# mbgw_teensy.net
KiCad netlist of a schematic drawn in EAGLE
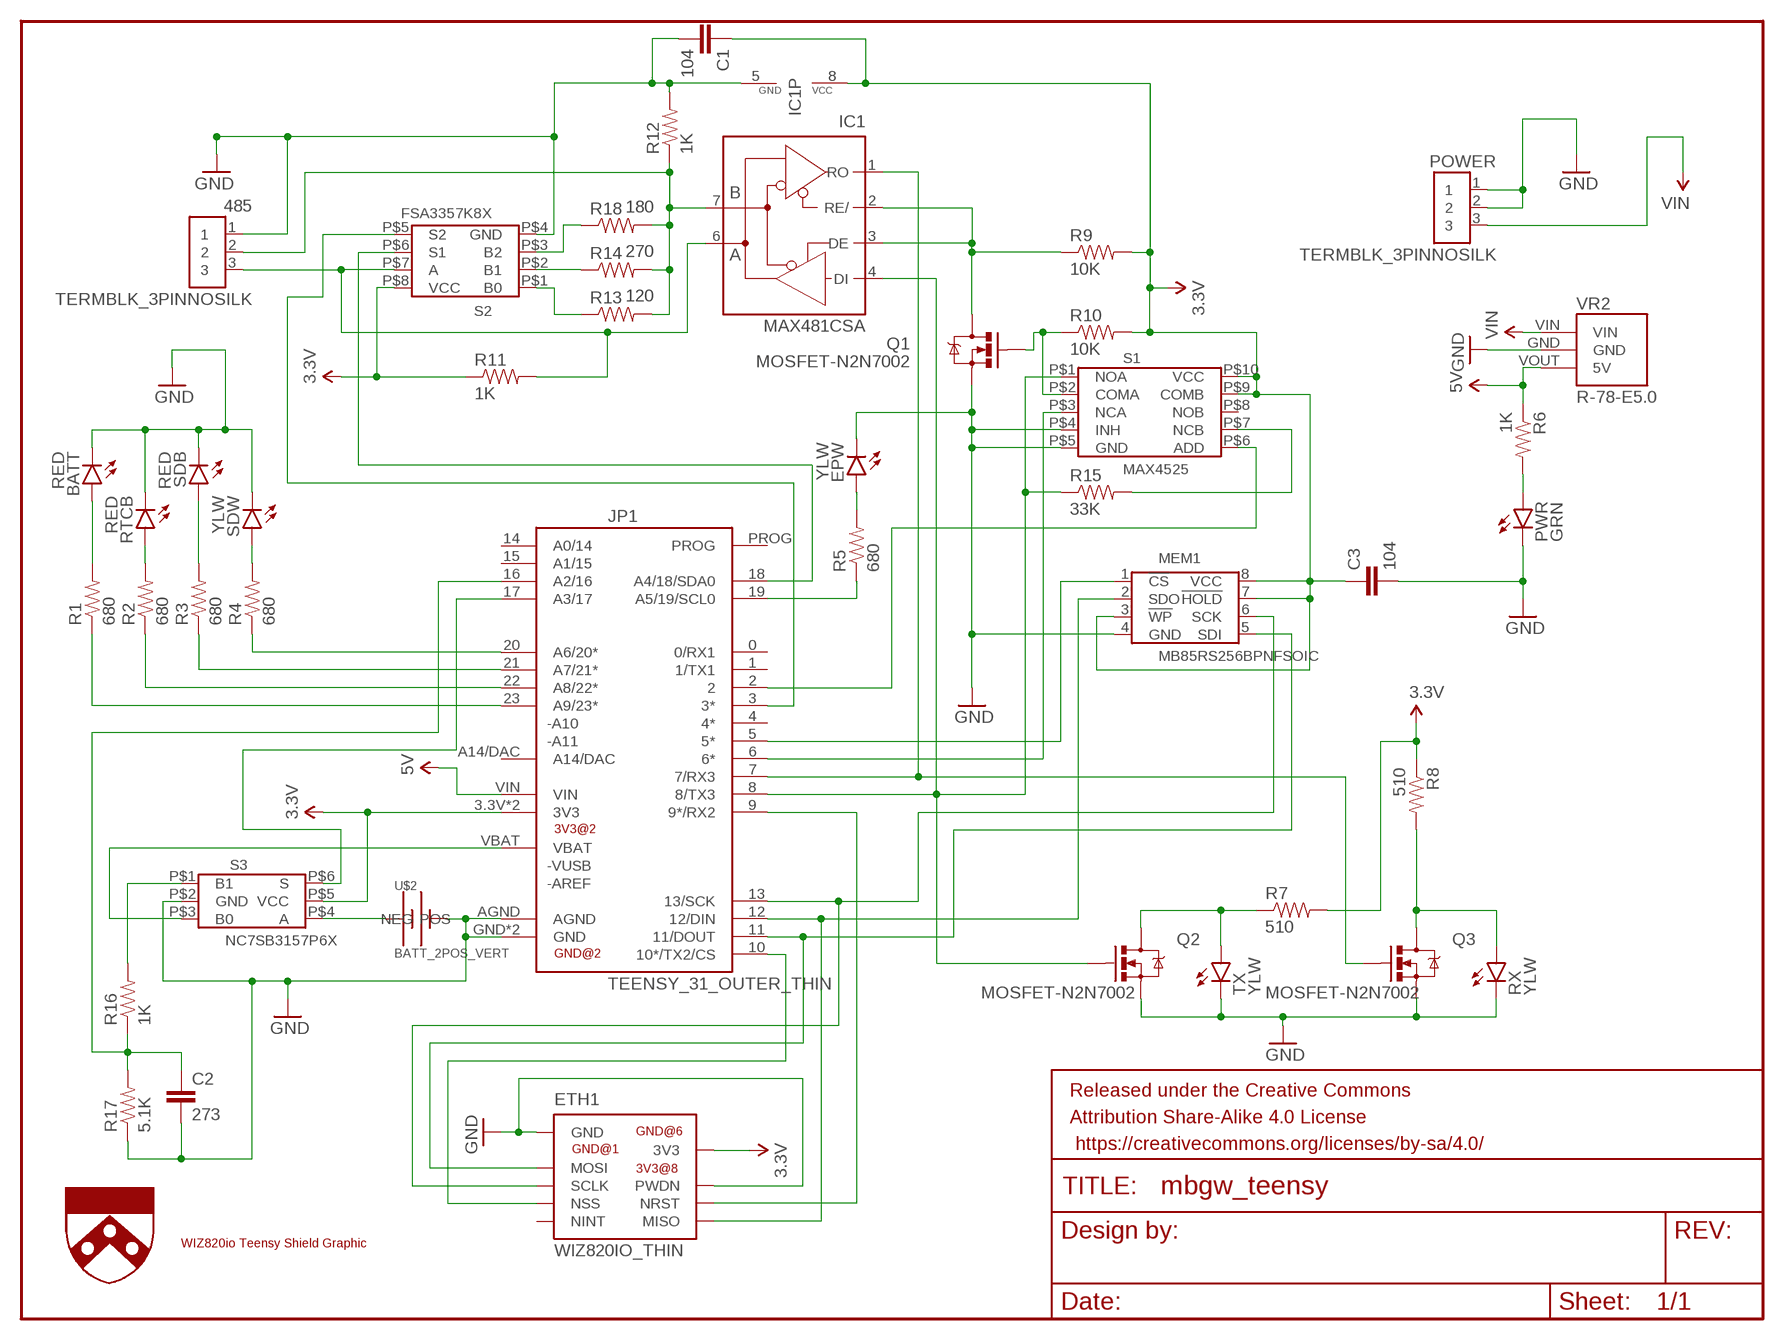
[diagram p0: schematic, sheet 1]

(export (version "E")
  (design (tool "Eeschema 10.0.6"))
  (components
    (comp (ref "485")
      (value "TERMBLK_3PINNOSILK")
      (footprint "eagle-import:TERMBLK_3PIN_90_NOSILK")
      (libsource (lib "eagle-import") (part "TERMBLK_3PINNOSILK"))
    )
    (comp (ref "BATT")
      (value "RED")
      (footprint "eagle-import:LED-0603")
      (libsource (lib "eagle-import") (part "LED0603"))
    )
    (comp (ref "C1")
      (value "104")
      (footprint "eagle-import:0603-CAP")
      (libsource (lib "eagle-import") (part "CAP0603-CAP"))
    )
    (comp (ref "C2")
      (value "273")
      (footprint "eagle-import:0603-CAP")
      (libsource (lib "eagle-import") (part "CAP0603-CAP"))
    )
    (comp (ref "C3")
      (value "104")
      (footprint "eagle-import:0603-CAP")
      (libsource (lib "eagle-import") (part "CAP0603-CAP"))
    )
    (comp (ref "EPW")
      (value "YLW")
      (footprint "eagle-import:LED-0603")
      (libsource (lib "eagle-import") (part "LED0603"))
    )
    (comp (ref "ETH1")
      (value "WIZ820IO_THIN")
      (footprint "eagle-import:WIZ820IO_THIN")
      (libsource (lib "eagle-import") (part "WIZ820IO_THIN"))
    )
    (comp (ref "FRAME1")
      (value "FRAME-LETTERNO_PACKAGE")
      (footprint "eagle-import:DUMMY")
      (fields (field (name "DESIGNER") "Nobody"))
      (libsource (lib "eagle-import") (part "FRAME-LETTERNO_PACKAGE"))
    )
    (comp (ref "IC1")
      (value "MAX481CSA")
      (footprint "eagle-import:SO08")
      (fields (field (name "MF") "MAXIM"))
      (libsource (lib "eagle-import") (part "MAX481CSA"))
    )
    (comp (ref "JP1")
      (value "TEENSY_31_OUTER_THIN")
      (footprint "eagle-import:TEENSY-3.1_OUTER_THIN")
      (libsource (lib "eagle-import") (part "TEENSY_31_OUTER_THIN"))
    )
    (comp (ref "MEM1")
      (value "MB85RS256BPNFSOIC")
      (footprint "eagle-import:SO08")
      (libsource (lib "eagle-import") (part "MB85RS256BPNFSOIC"))
    )
    (comp (ref "POWER")
      (value "TERMBLK_3PINNOSILK")
      (footprint "eagle-import:TERMBLK_3PIN_90_NOSILK")
      (libsource (lib "eagle-import") (part "TERMBLK_3PINNOSILK"))
    )
    (comp (ref "PWR")
      (value "GRN")
      (footprint "eagle-import:LED-0603")
      (libsource (lib "eagle-import") (part "LED0603"))
    )
    (comp (ref "Q1")
      (value "MOSFET-N2N7002")
      (footprint "eagle-import:SOT23-3")
      (libsource (lib "eagle-import") (part "MOSFET-N2N7002"))
    )
    (comp (ref "Q2")
      (value "MOSFET-N2N7002")
      (footprint "eagle-import:SOT23-3")
      (libsource (lib "eagle-import") (part "MOSFET-N2N7002"))
    )
    (comp (ref "Q3")
      (value "MOSFET-N2N7002")
      (footprint "eagle-import:SOT23-3")
      (libsource (lib "eagle-import") (part "MOSFET-N2N7002"))
    )
    (comp (ref "R1")
      (value "680")
      (footprint "eagle-import:0603-RES")
      (libsource (lib "eagle-import") (part "RESISTOR0603"))
    )
    (comp (ref "R2")
      (value "680")
      (footprint "eagle-import:0603-RES")
      (libsource (lib "eagle-import") (part "RESISTOR0603"))
    )
    (comp (ref "R3")
      (value "680")
      (footprint "eagle-import:0603-RES")
      (libsource (lib "eagle-import") (part "RESISTOR0603"))
    )
    (comp (ref "R4")
      (value "680")
      (footprint "eagle-import:0603-RES")
      (libsource (lib "eagle-import") (part "RESISTOR0603"))
    )
    (comp (ref "R5")
      (value "680")
      (footprint "eagle-import:0603-RES")
      (libsource (lib "eagle-import") (part "RESISTOR0603"))
    )
    (comp (ref "R6")
      (value "1K")
      (footprint "eagle-import:0603-RES")
      (libsource (lib "eagle-import") (part "RESISTOR0603"))
    )
    (comp (ref "R7")
      (value "510")
      (footprint "eagle-import:0603-RES")
      (libsource (lib "eagle-import") (part "RESISTOR0603"))
    )
    (comp (ref "R8")
      (value "510")
      (footprint "eagle-import:0603-RES")
      (libsource (lib "eagle-import") (part "RESISTOR0603"))
    )
    (comp (ref "R9")
      (value "10K")
      (footprint "eagle-import:0603-RES")
      (libsource (lib "eagle-import") (part "RESISTOR0603"))
    )
    (comp (ref "R10")
      (value "10K")
      (footprint "eagle-import:0603-RES")
      (libsource (lib "eagle-import") (part "RESISTOR0603"))
    )
    (comp (ref "R11")
      (value "1K")
      (footprint "eagle-import:0603-RES")
      (libsource (lib "eagle-import") (part "RESISTOR0603"))
    )
    (comp (ref "R12")
      (value "1K")
      (footprint "eagle-import:0603-RES")
      (libsource (lib "eagle-import") (part "RESISTOR0603"))
    )
    (comp (ref "R13")
      (value "120")
      (footprint "eagle-import:0603-RES")
      (libsource (lib "eagle-import") (part "RESISTOR0603"))
    )
    (comp (ref "R14")
      (value "270")
      (footprint "eagle-import:0603-RES")
      (libsource (lib "eagle-import") (part "RESISTOR0603"))
    )
    (comp (ref "R15")
      (value "33K")
      (footprint "eagle-import:0603-RES")
      (libsource (lib "eagle-import") (part "RESISTOR0603"))
    )
    (comp (ref "R16")
      (value "1K")
      (footprint "eagle-import:0603-RES")
      (libsource (lib "eagle-import") (part "RESISTOR0603"))
    )
    (comp (ref "R17")
      (value "5.1K")
      (footprint "eagle-import:0603-RES")
      (libsource (lib "eagle-import") (part "RESISTOR0603"))
    )
    (comp (ref "R18")
      (value "180")
      (footprint "eagle-import:0603-RES")
      (libsource (lib "eagle-import") (part "RESISTOR0603"))
    )
    (comp (ref "RTCB")
      (value "RED")
      (footprint "eagle-import:LED-0603")
      (libsource (lib "eagle-import") (part "LED0603"))
    )
    (comp (ref "RX")
      (value "YLW")
      (footprint "eagle-import:LED-0603")
      (libsource (lib "eagle-import") (part "LED0603"))
    )
    (comp (ref "S1")
      (value "MAX4525")
      (footprint "eagle-import:3MM_10PIN")
      (libsource (lib "eagle-import") (part "MAX4525"))
    )
    (comp (ref "S2")
      (value "FSA3357K8X")
      (footprint "eagle-import:2.3MM_8PIN")
      (libsource (lib "eagle-import") (part "FSA3357K8X"))
    )
    (comp (ref "S3")
      (value "NC7SB3157P6X")
      (footprint "eagle-import:1.25MM_6PIN")
      (libsource (lib "eagle-import") (part "NC7SB3157P6X"))
    )
    (comp (ref "SDB")
      (value "RED")
      (footprint "eagle-import:LED-0603")
      (libsource (lib "eagle-import") (part "LED0603"))
    )
    (comp (ref "SDW")
      (value "YLW")
      (footprint "eagle-import:LED-0603")
      (libsource (lib "eagle-import") (part "LED0603"))
    )
    (comp (ref "TX")
      (value "YLW")
      (footprint "eagle-import:LED-0603")
      (libsource (lib "eagle-import") (part "LED0603"))
    )
    (comp (ref "U$1")
      (value "WIZ820_SHLD_OVRLY")
      (footprint "eagle-import:WIZ820_SHLD_OVERLAY")
      (libsource (lib "eagle-import") (part "WIZ820_SHLD_OVRLY"))
    )
    (comp (ref "U$2")
      (value "BATT_2POS_VERT")
      (footprint "eagle-import:BATTCONN_20MM_VERT")
      (libsource (lib "eagle-import") (part "BATT_2POS_VERT"))
    )
    (comp (ref "U$4")
      (value "UPENN_SHIELD_.3_SILK")
      (footprint "eagle-import:UPENN_SHIELD_3_SILK")
      (libsource (lib "eagle-import") (part "UPENN_SHIELD_.3_SILK"))
    )
    (comp (ref "VR2")
      (value "R-78-E5.0")
      (footprint "eagle-import:R-78-EXX")
      (libsource (lib "eagle-import") (part "R-78-E5.0"))
    )
  )
  (nets
    (net (code "1") (name "3.3V") (class "Default")
      (node (ref "C1") (pin "1") (pinfunction "1_1") (pintype "passive"))
      (node (ref "C3") (pin "1") (pinfunction "1_1") (pintype "passive"))
      (node (ref "ETH1") (pin "3V3@7") (pinfunction "3V3_3V3@7") (pintype "power_in"))
      (node (ref "ETH1") (pin "3V3@8") (pinfunction "3V3_3V3@8") (pintype "power_in"))
      (node (ref "IC1") (pin "8") (pinfunction "VCC_8") (pintype "power_in"))
      (node (ref "JP1") (pin "3.3V") (pinfunction "3V3_3.3V") (pintype "power_in"))
      (node (ref "JP1") (pin "3V") (pinfunction "3V3_3V") (pintype "power_in"))
      (node (ref "MEM1") (pin "3") (pinfunction "~{WP}_3") (pintype "bidirectional"))
      (node (ref "MEM1") (pin "7") (pinfunction "~{HOLD}_7") (pintype "bidirectional"))
      (node (ref "MEM1") (pin "8") (pinfunction "VCC_8") (pintype "bidirectional"))
      (node (ref "R10") (pin "2") (pinfunction "2_2") (pintype "passive"))
      (node (ref "R11") (pin "1") (pinfunction "1_1") (pintype "passive"))
      (node (ref "R7") (pin "2") (pinfunction "2_2") (pintype "passive"))
      (node (ref "R8") (pin "1") (pinfunction "1_1") (pintype "passive"))
      (node (ref "R9") (pin "2") (pinfunction "2_2") (pintype "passive"))
      (node (ref "S1") (pin "P$10") (pinfunction "VCC_P$10") (pintype "bidirectional"))
      (node (ref "S1") (pin "P$9") (pinfunction "COMB_P$9") (pintype "bidirectional"))
      (node (ref "S2") (pin "P$8") (pinfunction "VCC_P$8") (pintype "bidirectional"))
      (node (ref "S3") (pin "P$5") (pinfunction "VCC_P$5") (pintype "bidirectional"))
    )
    (net (code "2") (name "5V") (class "Default")
      (node (ref "JP1") (pin "VIN") (pinfunction "VIN_VIN") (pintype "bidirectional"))
      (node (ref "R6") (pin "1") (pinfunction "1_1") (pintype "passive"))
      (node (ref "VR2") (pin "VOUT") (pinfunction "5V_VOUT") (pintype "bidirectional"))
    )
    (net (code "3") (name "GND") (class "Default")
      (node (ref "485") (pin "1") (pinfunction "1_1") (pintype "bidirectional"))
      (node (ref "BATT") (pin "C") (pinfunction "C_C") (pintype "passive"))
      (node (ref "C1") (pin "2") (pinfunction "2_2") (pintype "passive"))
      (node (ref "C2") (pin "2") (pinfunction "2_2") (pintype "passive"))
      (node (ref "C3") (pin "2") (pinfunction "2_2") (pintype "passive"))
      (node (ref "EPW") (pin "C") (pinfunction "C_C") (pintype "passive"))
      (node (ref "ETH1") (pin "GND@0") (pinfunction "GND_GND@0") (pintype "power_in"))
      (node (ref "ETH1") (pin "GND@1") (pinfunction "GND_GND@1") (pintype "power_in"))
      (node (ref "ETH1") (pin "GND@6") (pinfunction "GND_GND@6") (pintype "power_in"))
      (node (ref "ETH1") (pin "PWDN") (pinfunction "PWDN_PWDN") (pintype "bidirectional"))
      (node (ref "IC1") (pin "5") (pinfunction "GND_5") (pintype "power_in"))
      (node (ref "JP1") (pin "AGND") (pinfunction "AGND_AGND") (pintype "bidirectional"))
      (node (ref "JP1") (pin "GND") (pinfunction "GND_GND") (pintype "bidirectional"))
      (node (ref "JP1") (pin "GND1") (pinfunction "GND_GND1") (pintype "bidirectional"))
      (node (ref "MEM1") (pin "4") (pinfunction "GND_4") (pintype "bidirectional"))
      (node (ref "POWER") (pin "1") (pinfunction "1_1") (pintype "bidirectional"))
      (node (ref "POWER") (pin "2") (pinfunction "2_2") (pintype "bidirectional"))
      (node (ref "PWR") (pin "C") (pinfunction "C_C") (pintype "passive"))
      (node (ref "Q1") (pin "2") (pinfunction "S_2") (pintype "passive"))
      (node (ref "Q2") (pin "2") (pinfunction "S_2") (pintype "passive"))
      (node (ref "Q3") (pin "2") (pinfunction "S_2") (pintype "passive"))
      (node (ref "R12") (pin "2") (pinfunction "2_2") (pintype "passive"))
      (node (ref "R17") (pin "1") (pinfunction "1_1") (pintype "passive"))
      (node (ref "RTCB") (pin "C") (pinfunction "C_C") (pintype "passive"))
      (node (ref "RX") (pin "C") (pinfunction "C_C") (pintype "passive"))
      (node (ref "S1") (pin "P$4") (pinfunction "INH_P$4") (pintype "bidirectional"))
      (node (ref "S1") (pin "P$5") (pinfunction "GND_P$5") (pintype "bidirectional"))
      (node (ref "S2") (pin "P$4") (pinfunction "GND_P$4") (pintype "bidirectional"))
      (node (ref "S3") (pin "P$2") (pinfunction "GND_P$2") (pintype "bidirectional"))
      (node (ref "SDB") (pin "C") (pinfunction "C_C") (pintype "passive"))
      (node (ref "SDW") (pin "C") (pinfunction "C_C") (pintype "passive"))
      (node (ref "TX") (pin "C") (pinfunction "C_C") (pintype "passive"))
      (node (ref "U$2") (pin "NEG") (pinfunction "NEG_NEG") (pintype "bidirectional"))
      (node (ref "VR2") (pin "GND") (pinfunction "GND_GND") (pintype "bidirectional"))
    )
    (net (code "4") (name "Net-(BATT-PadA)") (class "Default")
      (node (ref "BATT") (pin "A") (pinfunction "A_A") (pintype "passive"))
      (node (ref "R1") (pin "2") (pinfunction "2_2") (pintype "passive"))
    )
    (net (code "5") (name "Net-(EPW-PadA)") (class "Default")
      (node (ref "EPW") (pin "A") (pinfunction "A_A") (pintype "passive"))
      (node (ref "R5") (pin "2") (pinfunction "2_2") (pintype "passive"))
    )
    (net (code "6") (name "Net-(IC1A-A)") (class "Default")
      (node (ref "485") (pin "3") (pinfunction "3_3") (pintype "bidirectional"))
      (node (ref "IC1") (pin "6") (pinfunction "A_6") (pintype "passive"))
      (node (ref "R11") (pin "2") (pinfunction "2_2") (pintype "passive"))
      (node (ref "S2") (pin "P$7") (pinfunction "A_P$7") (pintype "bidirectional"))
    )
    (net (code "7") (name "Net-(IC1A-B)") (class "Default")
      (node (ref "485") (pin "2") (pinfunction "2_2") (pintype "bidirectional"))
      (node (ref "IC1") (pin "7") (pinfunction "B_7") (pintype "passive"))
      (node (ref "R12") (pin "1") (pinfunction "1_1") (pintype "passive"))
      (node (ref "R13") (pin "2") (pinfunction "2_2") (pintype "passive"))
      (node (ref "R14") (pin "2") (pinfunction "2_2") (pintype "passive"))
      (node (ref "R18") (pin "2") (pinfunction "2_2") (pintype "passive"))
    )
    (net (code "8") (name "Net-(IC1A-DE)") (class "Default")
      (node (ref "IC1") (pin "2") (pinfunction "RE/_2") (pintype "input"))
      (node (ref "IC1") (pin "3") (pinfunction "DE_3") (pintype "input"))
      (node (ref "Q1") (pin "3") (pinfunction "D_3") (pintype "passive"))
      (node (ref "R9") (pin "1") (pinfunction "1_1") (pintype "passive"))
    )
    (net (code "9") (name "Net-(IC1A-DI)") (class "Default")
      (node (ref "IC1") (pin "4") (pinfunction "DI_4") (pintype "input"))
      (node (ref "JP1") (pin "8") (pinfunction "8/TX3_8") (pintype "bidirectional"))
      (node (ref "Q2") (pin "1") (pinfunction "G_1") (pintype "passive"))
      (node (ref "R15") (pin "1") (pinfunction "1_1") (pintype "passive"))
      (node (ref "S1") (pin "P$1") (pinfunction "NOA_P$1") (pintype "bidirectional"))
    )
    (net (code "10") (name "Net-(IC1A-RO)") (class "Default")
      (node (ref "IC1") (pin "1") (pinfunction "RO_1") (pintype "output"))
      (node (ref "JP1") (pin "7") (pinfunction "7/RX3_7") (pintype "bidirectional"))
      (node (ref "Q3") (pin "1") (pinfunction "G_1") (pintype "passive"))
    )
    (net (code "11") (name "Net-(JP1-3*)") (class "Default")
      (node (ref "JP1") (pin "3") (pinfunction "3*_3") (pintype "bidirectional"))
      (node (ref "S2") (pin "P$5") (pinfunction "S2_P$5") (pintype "bidirectional"))
    )
    (net (code "12") (name "Net-(JP1-5*)") (class "Default")
      (node (ref "JP1") (pin "5") (pinfunction "5*_5") (pintype "bidirectional"))
      (node (ref "MEM1") (pin "1") (pinfunction "~{CS}_1") (pintype "bidirectional"))
    )
    (net (code "13") (name "Net-(JP1-6*)") (class "Default")
      (node (ref "JP1") (pin "6") (pinfunction "6*_6") (pintype "bidirectional"))
      (node (ref "S1") (pin "P$3") (pinfunction "NCA_P$3") (pintype "bidirectional"))
    )
    (net (code "14") (name "Net-(JP1-9*{slash}RX2)") (class "Default")
      (node (ref "ETH1") (pin "NRST") (pinfunction "NRST_NRST") (pintype "bidirectional"))
      (node (ref "JP1") (pin "9") (pinfunction "9*/RX2_9") (pintype "bidirectional"))
    )
    (net (code "15") (name "Net-(JP1-10*{slash}TX2{slash}CS)") (class "Default")
      (node (ref "ETH1") (pin "NSS") (pinfunction "NSS_NSS") (pintype "bidirectional"))
      (node (ref "JP1") (pin "10") (pinfunction "10*/TX2/CS_10") (pintype "bidirectional"))
    )
    (net (code "16") (name "Net-(JP1-11{slash}DOUT)") (class "Default")
      (node (ref "ETH1") (pin "MOSI") (pinfunction "MOSI_MOSI") (pintype "bidirectional"))
      (node (ref "JP1") (pin "11") (pinfunction "11/DOUT_11") (pintype "bidirectional"))
      (node (ref "MEM1") (pin "5") (pinfunction "SDI_5") (pintype "bidirectional"))
    )
    (net (code "17") (name "Net-(JP1-12{slash}DIN)") (class "Default")
      (node (ref "ETH1") (pin "MISO") (pinfunction "MISO_MISO") (pintype "bidirectional"))
      (node (ref "JP1") (pin "12") (pinfunction "12/DIN_12") (pintype "bidirectional"))
      (node (ref "MEM1") (pin "2") (pinfunction "SDO_2") (pintype "bidirectional"))
    )
    (net (code "18") (name "Net-(JP1-13{slash}SCK)") (class "Default")
      (node (ref "ETH1") (pin "SCLK") (pinfunction "SCLK_SCLK") (pintype "bidirectional"))
      (node (ref "JP1") (pin "13") (pinfunction "13/SCK_13") (pintype "bidirectional"))
      (node (ref "MEM1") (pin "6") (pinfunction "SCK_6") (pintype "bidirectional"))
    )
    (net (code "19") (name "Net-(JP1-A2{slash}16)") (class "Default")
      (node (ref "C2") (pin "1") (pinfunction "1_1") (pintype "passive"))
      (node (ref "JP1") (pin "16") (pinfunction "A2/16_16") (pintype "bidirectional"))
      (node (ref "R16") (pin "1") (pinfunction "1_1") (pintype "passive"))
      (node (ref "R17") (pin "2") (pinfunction "2_2") (pintype "passive"))
    )
    (net (code "20") (name "Net-(JP1-A3{slash}17)") (class "Default")
      (node (ref "JP1") (pin "17") (pinfunction "A3/17_17") (pintype "bidirectional"))
      (node (ref "S3") (pin "P$6") (pinfunction "S_P$6") (pintype "bidirectional"))
    )
    (net (code "21") (name "Net-(JP1-A4{slash}18{slash}SDA0)") (class "Default")
      (node (ref "JP1") (pin "18") (pinfunction "A4/18/SDA0_18") (pintype "bidirectional"))
      (node (ref "S2") (pin "P$6") (pinfunction "S1_P$6") (pintype "bidirectional"))
    )
    (net (code "22") (name "Net-(JP1-A5{slash}19{slash}SCL0)") (class "Default")
      (node (ref "JP1") (pin "19") (pinfunction "A5/19/SCL0_19") (pintype "bidirectional"))
      (node (ref "R5") (pin "1") (pinfunction "1_1") (pintype "passive"))
    )
    (net (code "23") (name "Net-(JP1-A6{slash}20*)") (class "Default")
      (node (ref "JP1") (pin "20") (pinfunction "A6/20*_20") (pintype "bidirectional"))
      (node (ref "R4") (pin "1") (pinfunction "1_1") (pintype "passive"))
    )
    (net (code "24") (name "Net-(JP1-A7{slash}21*)") (class "Default")
      (node (ref "JP1") (pin "21") (pinfunction "A7/21*_21") (pintype "bidirectional"))
      (node (ref "R3") (pin "1") (pinfunction "1_1") (pintype "passive"))
    )
    (net (code "25") (name "Net-(JP1-A8{slash}22*)") (class "Default")
      (node (ref "JP1") (pin "22") (pinfunction "A8/22*_22") (pintype "bidirectional"))
      (node (ref "R2") (pin "1") (pinfunction "1_1") (pintype "passive"))
    )
    (net (code "26") (name "Net-(JP1-A9{slash}23*)") (class "Default")
      (node (ref "JP1") (pin "23") (pinfunction "A9/23*_23") (pintype "bidirectional"))
      (node (ref "R1") (pin "1") (pinfunction "1_1") (pintype "passive"))
    )
    (net (code "27") (name "Net-(PWR-PadA)") (class "Default")
      (node (ref "PWR") (pin "A") (pinfunction "A_A") (pintype "passive"))
      (node (ref "R6") (pin "2") (pinfunction "2_2") (pintype "passive"))
    )
    (net (code "28") (name "Net-(Q1-G)") (class "Default")
      (node (ref "Q1") (pin "1") (pinfunction "G_1") (pintype "passive"))
      (node (ref "R10") (pin "1") (pinfunction "1_1") (pintype "passive"))
      (node (ref "S1") (pin "P$2") (pinfunction "COMA_P$2") (pintype "bidirectional"))
    )
    (net (code "29") (name "Net-(Q2-D)") (class "Default")
      (node (ref "Q2") (pin "3") (pinfunction "D_3") (pintype "passive"))
      (node (ref "R7") (pin "1") (pinfunction "1_1") (pintype "passive"))
      (node (ref "TX") (pin "A") (pinfunction "A_A") (pintype "passive"))
    )
    (net (code "30") (name "Net-(Q3-D)") (class "Default")
      (node (ref "Q3") (pin "3") (pinfunction "D_3") (pintype "passive"))
      (node (ref "R8") (pin "2") (pinfunction "2_2") (pintype "passive"))
      (node (ref "RX") (pin "A") (pinfunction "A_A") (pintype "passive"))
    )
    (net (code "31") (name "Net-(R2-Pad2)") (class "Default")
      (node (ref "R2") (pin "2") (pinfunction "2_2") (pintype "passive"))
      (node (ref "RTCB") (pin "A") (pinfunction "A_A") (pintype "passive"))
    )
    (net (code "32") (name "Net-(R3-Pad2)") (class "Default")
      (node (ref "R3") (pin "2") (pinfunction "2_2") (pintype "passive"))
      (node (ref "SDB") (pin "A") (pinfunction "A_A") (pintype "passive"))
    )
    (net (code "33") (name "Net-(R4-Pad2)") (class "Default")
      (node (ref "R4") (pin "2") (pinfunction "2_2") (pintype "passive"))
      (node (ref "SDW") (pin "A") (pinfunction "A_A") (pintype "passive"))
    )
    (net (code "34") (name "Net-(S1-ADD)") (class "Default")
      (node (ref "JP1") (pin "2") (pinfunction "2_2") (pintype "bidirectional"))
      (node (ref "S1") (pin "P$6") (pinfunction "ADD_P$6") (pintype "bidirectional"))
    )
    (net (code "35") (name "Net-(S1-NCB)") (class "Default")
      (node (ref "R15") (pin "2") (pinfunction "2_2") (pintype "passive"))
      (node (ref "S1") (pin "P$7") (pinfunction "NCB_P$7") (pintype "bidirectional"))
    )
    (net (code "36") (name "Net-(S2-B0)") (class "Default")
      (node (ref "R13") (pin "1") (pinfunction "1_1") (pintype "passive"))
      (node (ref "S2") (pin "P$1") (pinfunction "B0_P$1") (pintype "bidirectional"))
    )
    (net (code "37") (name "Net-(S2-B1)") (class "Default")
      (node (ref "R14") (pin "1") (pinfunction "1_1") (pintype "passive"))
      (node (ref "S2") (pin "P$2") (pinfunction "B1_P$2") (pintype "bidirectional"))
    )
    (net (code "38") (name "Net-(S2-B2)") (class "Default")
      (node (ref "R18") (pin "1") (pinfunction "1_1") (pintype "passive"))
      (node (ref "S2") (pin "P$3") (pinfunction "B2_P$3") (pintype "bidirectional"))
    )
    (net (code "39") (name "Net-(S3-A)") (class "Default")
      (node (ref "S3") (pin "P$4") (pinfunction "A_P$4") (pintype "bidirectional"))
      (node (ref "U$2") (pin "POS@1") (pinfunction "POS_POS@1") (pintype "power_in"))
      (node (ref "U$2") (pin "POS@2") (pinfunction "POS_POS@2") (pintype "power_in"))
    )
    (net (code "40") (name "Net-(S3-B0)") (class "Default")
      (node (ref "JP1") (pin "VBAT") (pinfunction "VBAT_VBAT") (pintype "bidirectional"))
      (node (ref "S3") (pin "P$3") (pinfunction "B0_P$3") (pintype "bidirectional"))
    )
    (net (code "41") (name "Net-(S3-B1)") (class "Default")
      (node (ref "R16") (pin "2") (pinfunction "2_2") (pintype "passive"))
      (node (ref "S3") (pin "P$1") (pinfunction "B1_P$1") (pintype "bidirectional"))
    )
    (net (code "42") (name "VIN") (class "Default")
      (node (ref "POWER") (pin "3") (pinfunction "3_3") (pintype "bidirectional"))
      (node (ref "VR2") (pin "VIN") (pinfunction "VIN_VIN") (pintype "bidirectional"))
    )
    (net (code "43") (name "unconnected-(ETH1-PadNINT)") (class "Default")
      (node (ref "ETH1") (pin "NINT") (pinfunction "NINT_NINT") (pintype "bidirectional"))
    )
    (net (code "44") (name "unconnected-(JP1-0{slash}RX1-Pad0)") (class "Default")
      (node (ref "JP1") (pin "0") (pinfunction "0/RX1_0") (pintype "bidirectional"))
    )
    (net (code "45") (name "unconnected-(JP1-1{slash}TX1-Pad1)") (class "Default")
      (node (ref "JP1") (pin "1") (pinfunction "1/TX1_1") (pintype "bidirectional"))
    )
    (net (code "46") (name "unconnected-(JP1-4*-Pad4)") (class "Default")
      (node (ref "JP1") (pin "4") (pinfunction "4*_4") (pintype "bidirectional"))
    )
    (net (code "47") (name "unconnected-(JP1-A0{slash}14-Pad14)") (class "Default")
      (node (ref "JP1") (pin "14") (pinfunction "A0/14_14") (pintype "bidirectional"))
    )
    (net (code "48") (name "unconnected-(JP1-A1{slash}15-Pad15)") (class "Default")
      (node (ref "JP1") (pin "15") (pinfunction "A1/15_15") (pintype "bidirectional"))
    )
    (net (code "49") (name "unconnected-(JP1-PadA14{slash}DAC)") (class "Default")
      (node (ref "JP1") (pin "A14/DAC") (pinfunction "A14/DAC_A14/DAC") (pintype "bidirectional"))
    )
    (net (code "50") (name "unconnected-(JP1-PadPROG)") (class "Default")
      (node (ref "JP1") (pin "PROG") (pinfunction "PROG_PROG") (pintype "bidirectional"))
    )
    (net (code "51") (name "unconnected-(S1-NOB-PadP$8)") (class "Default")
      (node (ref "S1") (pin "P$8") (pinfunction "NOB_P$8") (pintype "bidirectional"))
    )
  )
)
